# DB9-Breakout.net
KiCad netlist of a schematic drawn in EAGLE
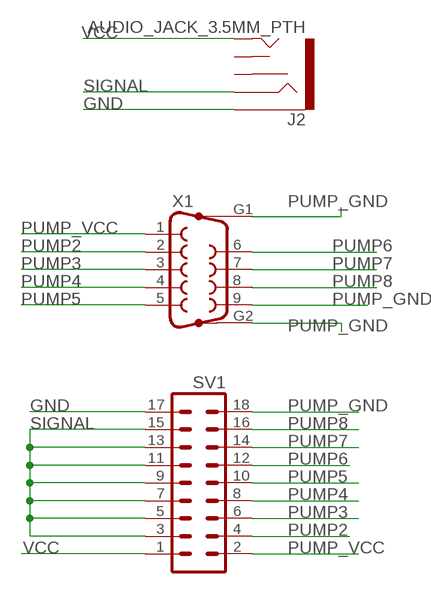
[diagram p0: schematic, sheet 1]

(export (version "E")
  (design (tool "Eeschema 10.0.6"))
  (components
    (comp (ref "J2")
      (value "AUDIO_JACK_3.5MM_PTH")
      (footprint "eagle-import:AUDIO-JACK")
      (libsource (lib "eagle-import") (part "AUDIO_JACK_3.5MM_PTH"))
    )
    (comp (ref "SV1")
      (value "MA09-2")
      (footprint "eagle-import:MA09-2")
      (libsource (lib "eagle-import") (part "MA09-2"))
    )
    (comp (ref "X1")
      (value "F09HP")
      (footprint "eagle-import:F09HP")
      (libsource (lib "eagle-import") (part "F09HP"))
    )
  )
  (nets
    (net (code "1") (name "/GND") (class "Default")
      (node (ref "J2") (pin "SLEEVE") (pinfunction "SLEEVE_SLEEVE") (pintype "bidirectional"))
      (node (ref "SV1") (pin "17") (pinfunction "17_17") (pintype "passive"))
    )
    (net (code "2") (name "/PUMP2") (class "Default")
      (node (ref "SV1") (pin "4") (pinfunction "4_4") (pintype "passive"))
      (node (ref "X1") (pin "2") (pinfunction "2_2") (pintype "passive"))
    )
    (net (code "3") (name "/PUMP3") (class "Default")
      (node (ref "SV1") (pin "6") (pinfunction "6_6") (pintype "passive"))
      (node (ref "X1") (pin "3") (pinfunction "3_3") (pintype "passive"))
    )
    (net (code "4") (name "/PUMP4") (class "Default")
      (node (ref "SV1") (pin "8") (pinfunction "8_8") (pintype "passive"))
      (node (ref "X1") (pin "4") (pinfunction "4_4") (pintype "passive"))
    )
    (net (code "5") (name "/PUMP5") (class "Default")
      (node (ref "SV1") (pin "10") (pinfunction "10_10") (pintype "passive"))
      (node (ref "X1") (pin "5") (pinfunction "5_5") (pintype "passive"))
    )
    (net (code "6") (name "/PUMP6") (class "Default")
      (node (ref "SV1") (pin "12") (pinfunction "12_12") (pintype "passive"))
      (node (ref "X1") (pin "6") (pinfunction "6_6") (pintype "passive"))
    )
    (net (code "7") (name "/PUMP7") (class "Default")
      (node (ref "SV1") (pin "14") (pinfunction "14_14") (pintype "passive"))
      (node (ref "X1") (pin "7") (pinfunction "7_7") (pintype "passive"))
    )
    (net (code "8") (name "/PUMP8") (class "Default")
      (node (ref "SV1") (pin "16") (pinfunction "16_16") (pintype "passive"))
      (node (ref "X1") (pin "8") (pinfunction "8_8") (pintype "passive"))
    )
    (net (code "9") (name "/PUMP_GND") (class "Default")
      (node (ref "SV1") (pin "18") (pinfunction "18_18") (pintype "passive"))
      (node (ref "X1") (pin "9") (pinfunction "9_9") (pintype "passive"))
      (node (ref "X1") (pin "G1") (pinfunction "G1_G1") (pintype "passive"))
      (node (ref "X1") (pin "G2") (pinfunction "G2_G2") (pintype "passive"))
    )
    (net (code "10") (name "/PUMP_VCC") (class "Default")
      (node (ref "SV1") (pin "2") (pinfunction "2_2") (pintype "passive"))
      (node (ref "X1") (pin "1") (pinfunction "1_1") (pintype "passive"))
    )
    (net (code "11") (name "/SIGNAL") (class "Default")
      (node (ref "J2") (pin "RING") (pinfunction "RING_RING") (pintype "bidirectional"))
      (node (ref "SV1") (pin "11") (pinfunction "11_11") (pintype "passive"))
      (node (ref "SV1") (pin "13") (pinfunction "13_13") (pintype "passive"))
      (node (ref "SV1") (pin "15") (pinfunction "15_15") (pintype "passive"))
      (node (ref "SV1") (pin "3") (pinfunction "3_3") (pintype "passive"))
      (node (ref "SV1") (pin "5") (pinfunction "5_5") (pintype "passive"))
      (node (ref "SV1") (pin "7") (pinfunction "7_7") (pintype "passive"))
      (node (ref "SV1") (pin "9") (pinfunction "9_9") (pintype "passive"))
    )
    (net (code "12") (name "/VCC") (class "Default")
      (node (ref "J2") (pin "TIP") (pinfunction "TIP_TIP") (pintype "bidirectional"))
      (node (ref "SV1") (pin "1") (pinfunction "1_1") (pintype "passive"))
    )
    (net (code "13") (name "unconnected-(J2-PadRSH)") (class "Default")
      (node (ref "J2") (pin "RSH") (pinfunction "RSH_RSH") (pintype "bidirectional"))
    )
    (net (code "14") (name "unconnected-(J2-PadTSH)") (class "Default")
      (node (ref "J2") (pin "TSH") (pinfunction "TSH_TSH") (pintype "bidirectional"))
    )
  )
)
